# Programming_Jack.net
KiCad netlist of a schematic drawn in Altium Designer
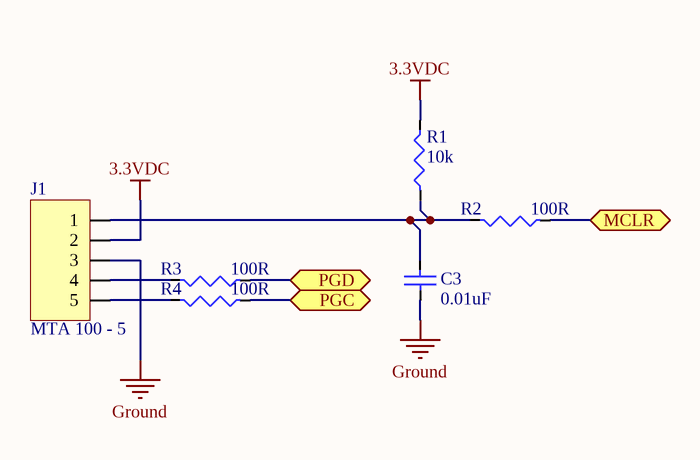
[diagram p0: Programming Jack.SchDoc]

(export (version "E")
  (design (tool "Eeschema 10.0.6"))
  (components
    (comp (ref "C3")
      (value "Capacitor (Non-polarized)")
      (footprint "Capacitor - 0603")
      (description "Non-polarized")
      (fields
        (field (name "TOLERANCE") "10%")
        (field (name "VOLTAGE") "50V")
        (field (name "QUICKVALUE") "0.01uF")
      )
      (libsource (lib "EDC Standard Library") (part "Capacitor (Non-polarized)"))
    )
    (comp (ref "J1")
      (value "Flash connector, 5 Position")
      (footprint "MTA-100-5P")
      (description "Flash header")
      (fields (field (name "QUICKVALUE") "MTA 100 - 5"))
      (libsource (lib "EDC Standard Library") (part "Flash connector, 5 Position"))
    )
    (comp (ref "R1")
      (value "Resistor")
      (footprint "RESISTOR THT 3W 0.05HOLE 900MIL")
      (fields (field (name "TOLERANCE") "1%") (field (name "QUICKVALUE") "10k"))
      (libsource (lib "EDC Standard Library") (part "Resistor"))
    )
    (comp (ref "R2")
      (value "Resistor")
      (footprint "Resistor - 0603")
      (fields (field (name "TOLERANCE") "1%") (field (name "QUICKVALUE") "100R"))
      (libsource (lib "EDC Standard Library") (part "Resistor"))
    )
    (comp (ref "R3")
      (value "Resistor")
      (footprint "Resistor - 0603")
      (fields (field (name "TOLERANCE") "1%") (field (name "QUICKVALUE") "100R"))
      (libsource (lib "EDC Standard Library") (part "Resistor"))
    )
    (comp (ref "R4")
      (value "Resistor")
      (footprint "Resistor - 0603")
      (fields (field (name "TOLERANCE") "1%") (field (name "QUICKVALUE") "100R"))
      (libsource (lib "EDC Standard Library") (part "Resistor"))
    )
  )
  (nets
    (net (code "1") (name "/MCLR") (class "Default")
      (node (ref "R2") (pin "1") (pinfunction "1_1") (pintype "passive"))
    )
    (net (code "2") (name "/PGC") (class "Default")
      (node (ref "R4") (pin "1") (pinfunction "1_1") (pintype "passive"))
    )
    (net (code "3") (name "/PGD") (class "Default")
      (node (ref "R3") (pin "1") (pinfunction "1_1") (pintype "passive"))
    )
    (net (code "4") (name "3.3VDC") (class "Default")
      (node (ref "J1") (pin "2") (pinfunction "2_2") (pintype "passive"))
      (node (ref "R1") (pin "2") (pinfunction "2_2") (pintype "passive"))
    )
    (net (code "5") (name "Ground") (class "Default")
      (node (ref "C3") (pin "2") (pinfunction "2_2") (pintype "passive"))
      (node (ref "J1") (pin "3") (pinfunction "3_3") (pintype "passive"))
    )
    (net (code "6") (name "Net-(C3-Pad1)") (class "Default")
      (node (ref "C3") (pin "1") (pinfunction "1_1") (pintype "passive"))
      (node (ref "J1") (pin "1") (pinfunction "1_1") (pintype "passive"))
      (node (ref "R1") (pin "1") (pinfunction "1_1") (pintype "passive"))
      (node (ref "R2") (pin "2") (pinfunction "2_2") (pintype "passive"))
    )
    (net (code "7") (name "Net-(J1-Pad4)") (class "Default")
      (node (ref "J1") (pin "4") (pinfunction "4_4") (pintype "passive"))
      (node (ref "R3") (pin "2") (pinfunction "2_2") (pintype "passive"))
    )
    (net (code "8") (name "Net-(J1-Pad5)") (class "Default")
      (node (ref "J1") (pin "5") (pinfunction "5_5") (pintype "passive"))
      (node (ref "R4") (pin "2") (pinfunction "2_2") (pintype "passive"))
    )
  )
)
